# WalkerStalkerv03.net
KiCad netlist of a schematic drawn in EAGLE
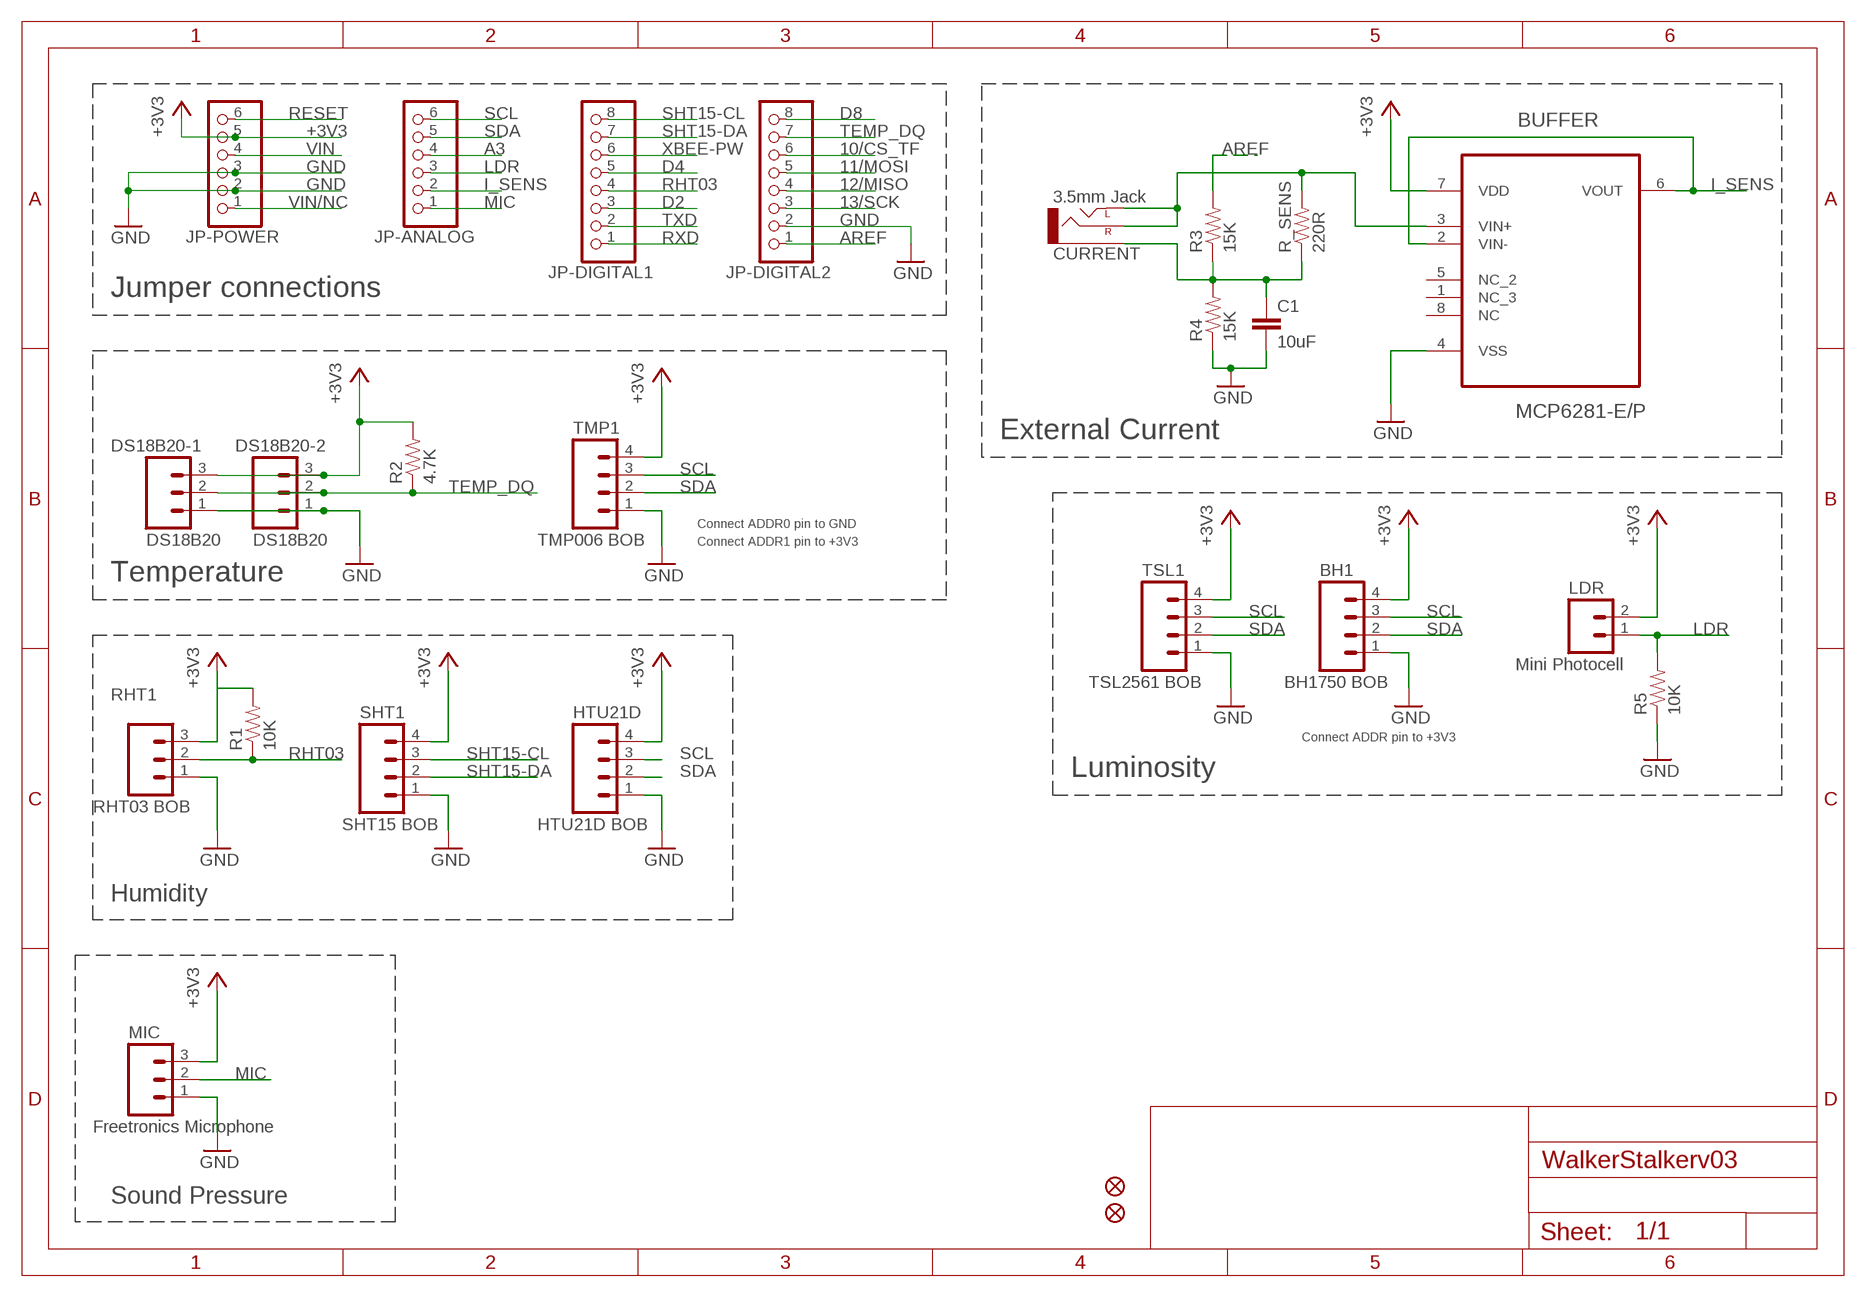
[diagram p0: schematic, sheet 1, part 1 of 2]
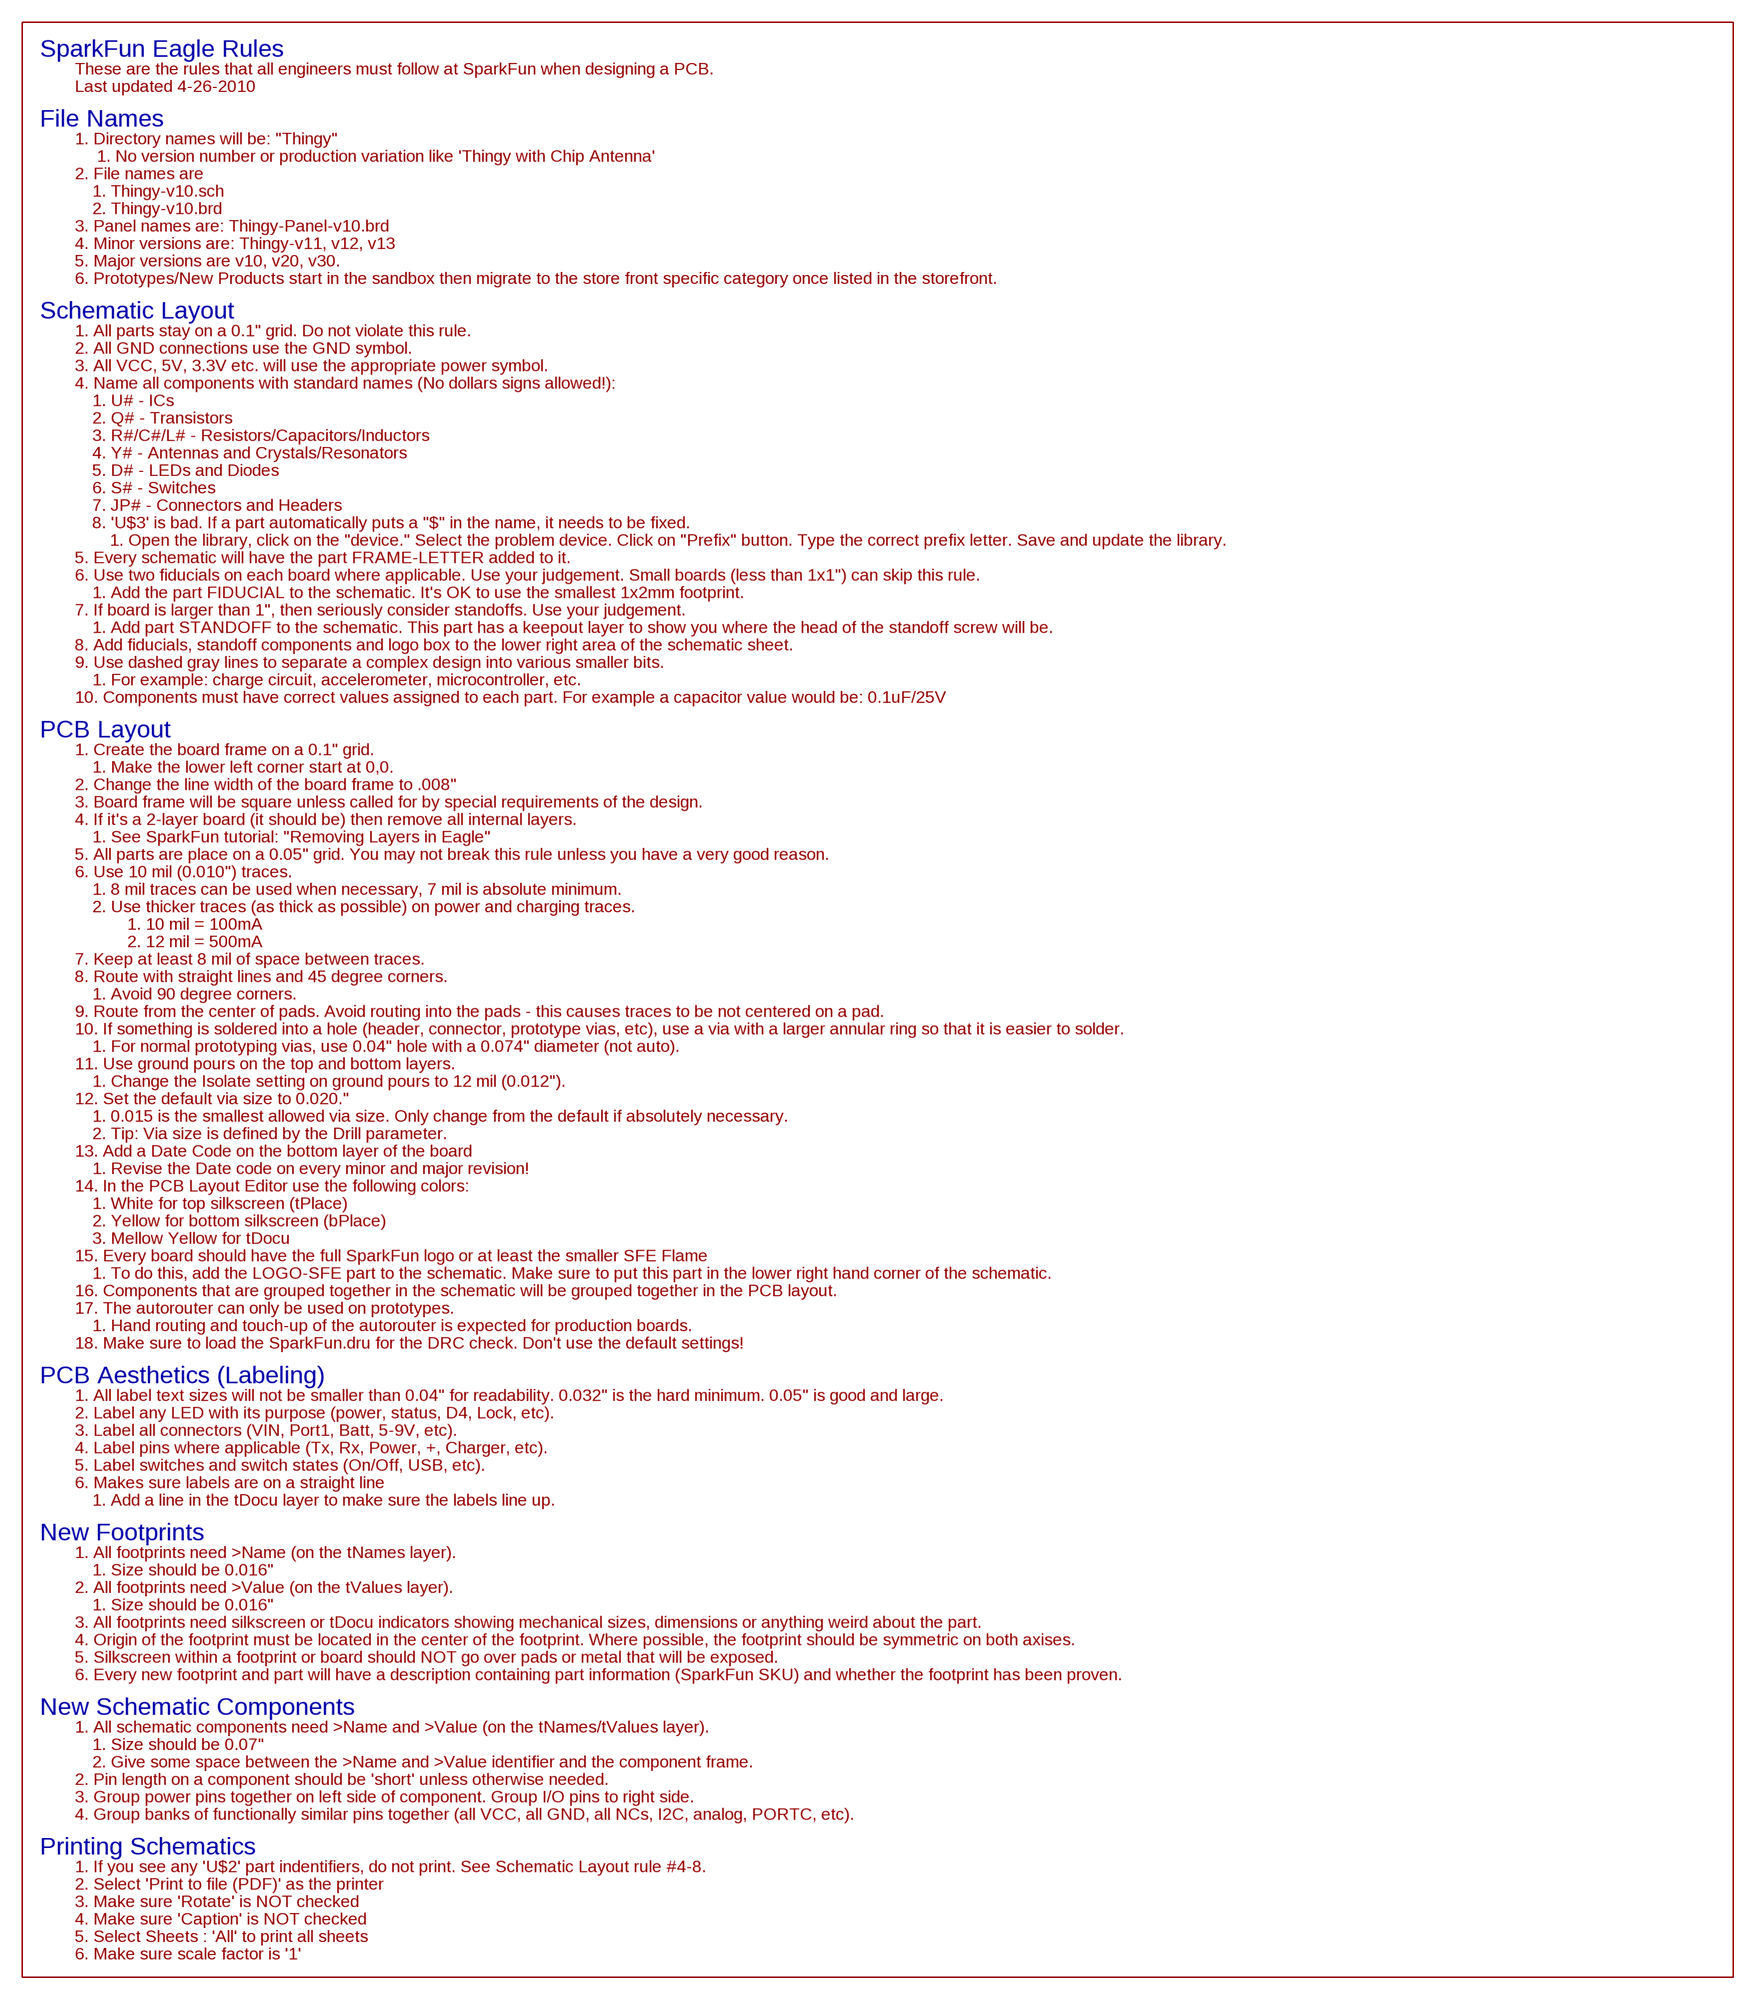
[diagram p1: schematic, sheet 1, part 2 of 2]

(export (version "E")
  (design (tool "Eeschema 10.0.6"))
  (components
    (comp (ref "BH1")
      (value "BH1750 BOB")
      (footprint "eagle-import:MOLEX-1X4")
      (libsource (lib "eagle-import") (part "M04POLAR"))
    )
    (comp (ref "BUFFER")
      (value "MCP6281-E/P")
      (footprint "eagle-import:DIP254P762X432-8")
      (libsource (lib "eagle-import") (part "MCP6281-E/P"))
    )
    (comp (ref "C1")
      (value "10uF")
      (footprint "eagle-import:1206")
      (libsource (lib "eagle-import") (part "CAP1206"))
    )
    (comp (ref "CURRENT")
      (value "3.5mm Jack")
      (footprint "eagle-import:AUDIO-JACK")
      (libsource (lib "eagle-import") (part "AUDIO-JACKPTH"))
    )
    (comp (ref "DS18B20-1")
      (value "DS18B20")
      (footprint "eagle-import:MOLEX-1X3")
      (libsource (lib "eagle-import") (part "M03POLAR"))
    )
    (comp (ref "DS18B20-2")
      (value "DS18B20")
      (footprint "eagle-import:MOLEX-1X3")
      (libsource (lib "eagle-import") (part "M03POLAR"))
    )
    (comp (ref "FID1")
      (value "FIDUCIAL1.5X3")
      (footprint "eagle-import:FIDUCIAL-1.5X3")
      (libsource (lib "eagle-import") (part "FIDUCIAL1.5X3"))
    )
    (comp (ref "FID2")
      (value "FIDUCIAL1.5X3")
      (footprint "eagle-import:FIDUCIAL-1.5X3")
      (libsource (lib "eagle-import") (part "FIDUCIAL1.5X3"))
    )
    (comp (ref "HTU21D")
      (value "HTU21D BOB")
      (footprint "eagle-import:MOLEX-1X4")
      (libsource (lib "eagle-import") (part "M04POLAR"))
    )
    (comp (ref "JP-ANALOG")
      (value "PINHD-1X6CB")
      (footprint "eagle-import:1X06-CLEANBIG")
      (libsource (lib "eagle-import") (part "PINHD-1X6CB"))
    )
    (comp (ref "JP-DIGITAL1")
      (value "PINHD-1X8CLEANBIG")
      (footprint "eagle-import:1X08-CLEANBIG")
      (libsource (lib "eagle-import") (part "PINHD-1X8CLEANBIG"))
    )
    (comp (ref "JP-DIGITAL2")
      (value "PINHD-1X8CLEANBIG")
      (footprint "eagle-import:1X08-CLEANBIG")
      (libsource (lib "eagle-import") (part "PINHD-1X8CLEANBIG"))
    )
    (comp (ref "JP-POWER")
      (value "PINHD-1X6CB")
      (footprint "eagle-import:1X06-CLEANBIG")
      (libsource (lib "eagle-import") (part "PINHD-1X6CB"))
    )
    (comp (ref "LDR")
      (value "Mini Photocell")
      (footprint "eagle-import:MOLEX-1X2")
      (libsource (lib "eagle-import") (part "M02POLAR"))
    )
    (comp (ref "MIC")
      (value "Freetronics Microphone")
      (footprint "eagle-import:MOLEX-1X3")
      (libsource (lib "eagle-import") (part "M03POLAR"))
    )
    (comp (ref "R1")
      (value "10K")
      (footprint "eagle-import:1206")
      (libsource (lib "eagle-import") (part "RESISTOR1206"))
    )
    (comp (ref "R2")
      (value "4.7K")
      (footprint "eagle-import:1206")
      (libsource (lib "eagle-import") (part "RESISTOR1206"))
    )
    (comp (ref "R3")
      (value "15K")
      (footprint "eagle-import:1206")
      (libsource (lib "eagle-import") (part "RESISTOR1206"))
    )
    (comp (ref "R4")
      (value "15K")
      (footprint "eagle-import:1206")
      (libsource (lib "eagle-import") (part "RESISTOR1206"))
    )
    (comp (ref "R5")
      (value "10K")
      (footprint "eagle-import:1206")
      (libsource (lib "eagle-import") (part "RESISTOR1206"))
    )
    (comp (ref "RHT1")
      (value "RHT03 BOB")
      (footprint "eagle-import:MOLEX-1X3")
      (libsource (lib "eagle-import") (part "M03POLAR"))
    )
    (comp (ref "R_SENS")
      (value "220R")
      (footprint "eagle-import:1206")
      (libsource (lib "eagle-import") (part "RESISTOR1206"))
    )
    (comp (ref "SHT1")
      (value "SHT15 BOB")
      (footprint "eagle-import:MOLEX-1X4")
      (libsource (lib "eagle-import") (part "M04POLAR"))
    )
    (comp (ref "TMP1")
      (value "TMP006 BOB")
      (footprint "eagle-import:MOLEX-1X4")
      (libsource (lib "eagle-import") (part "M04POLAR"))
    )
    (comp (ref "TSL1")
      (value "TSL2561 BOB")
      (footprint "eagle-import:MOLEX-1X4")
      (libsource (lib "eagle-import") (part "M04POLAR"))
    )
  )
  (nets
    (net (code "1") (name "+3V3") (class "Default")
      (node (ref "BH1") (pin "4") (pinfunction "4_4") (pintype "passive"))
      (node (ref "BUFFER") (pin "7") (pinfunction "VDD_7") (pintype "power_in"))
      (node (ref "DS18B20-1") (pin "3") (pinfunction "3_3") (pintype "passive"))
      (node (ref "DS18B20-2") (pin "3") (pinfunction "3_3") (pintype "passive"))
      (node (ref "HTU21D") (pin "4") (pinfunction "4_4") (pintype "passive"))
      (node (ref "JP-POWER") (pin "5") (pinfunction "5_5") (pintype "passive"))
      (node (ref "LDR") (pin "2") (pinfunction "2_2") (pintype "passive"))
      (node (ref "MIC") (pin "3") (pinfunction "3_3") (pintype "passive"))
      (node (ref "R1") (pin "2") (pinfunction "2_2") (pintype "passive"))
      (node (ref "R2") (pin "2") (pinfunction "2_2") (pintype "passive"))
      (node (ref "RHT1") (pin "3") (pinfunction "3_3") (pintype "passive"))
      (node (ref "SHT1") (pin "4") (pinfunction "4_4") (pintype "passive"))
      (node (ref "TMP1") (pin "4") (pinfunction "4_4") (pintype "passive"))
      (node (ref "TSL1") (pin "4") (pinfunction "4_4") (pintype "passive"))
    )
    (net (code "2") (name "/10{slash}CS_TF") (class "Default")
      (node (ref "JP-DIGITAL2") (pin "6") (pinfunction "6_6") (pintype "passive"))
    )
    (net (code "3") (name "/11{slash}MOSI") (class "Default")
      (node (ref "JP-DIGITAL2") (pin "5") (pinfunction "5_5") (pintype "passive"))
    )
    (net (code "4") (name "/12{slash}MISO") (class "Default")
      (node (ref "JP-DIGITAL2") (pin "4") (pinfunction "4_4") (pintype "passive"))
    )
    (net (code "5") (name "/13{slash}SCK") (class "Default")
      (node (ref "JP-DIGITAL2") (pin "3") (pinfunction "3_3") (pintype "passive"))
    )
    (net (code "6") (name "/A3") (class "Default")
      (node (ref "JP-ANALOG") (pin "4") (pinfunction "4_4") (pintype "passive"))
    )
    (net (code "7") (name "/AREF") (class "Default")
      (node (ref "JP-DIGITAL2") (pin "1") (pinfunction "1_1") (pintype "passive"))
      (node (ref "R3") (pin "2") (pinfunction "2_2") (pintype "passive"))
    )
    (net (code "8") (name "/D2") (class "Default")
      (node (ref "JP-DIGITAL1") (pin "3") (pinfunction "3_3") (pintype "passive"))
    )
    (net (code "9") (name "/D4") (class "Default")
      (node (ref "JP-DIGITAL1") (pin "5") (pinfunction "5_5") (pintype "passive"))
    )
    (net (code "10") (name "/D8") (class "Default")
      (node (ref "JP-DIGITAL2") (pin "8") (pinfunction "8_8") (pintype "passive"))
    )
    (net (code "11") (name "/I_SENS") (class "Default")
      (node (ref "BUFFER") (pin "2") (pinfunction "VIN-_2") (pintype "input"))
      (node (ref "BUFFER") (pin "6") (pinfunction "VOUT_6") (pintype "output"))
      (node (ref "JP-ANALOG") (pin "2") (pinfunction "2_2") (pintype "passive"))
    )
    (net (code "12") (name "/LDR") (class "Default")
      (node (ref "JP-ANALOG") (pin "3") (pinfunction "3_3") (pintype "passive"))
      (node (ref "LDR") (pin "1") (pinfunction "1_1") (pintype "passive"))
      (node (ref "R5") (pin "2") (pinfunction "2_2") (pintype "passive"))
    )
    (net (code "13") (name "/MIC") (class "Default")
      (node (ref "JP-ANALOG") (pin "1") (pinfunction "1_1") (pintype "passive"))
      (node (ref "MIC") (pin "2") (pinfunction "2_2") (pintype "passive"))
    )
    (net (code "14") (name "/RESET") (class "Default")
      (node (ref "JP-POWER") (pin "6") (pinfunction "6_6") (pintype "passive"))
    )
    (net (code "15") (name "/RHT03") (class "Default")
      (node (ref "JP-DIGITAL1") (pin "4") (pinfunction "4_4") (pintype "passive"))
      (node (ref "R1") (pin "1") (pinfunction "1_1") (pintype "passive"))
      (node (ref "RHT1") (pin "2") (pinfunction "2_2") (pintype "passive"))
    )
    (net (code "16") (name "/RXD") (class "Default")
      (node (ref "JP-DIGITAL1") (pin "1") (pinfunction "1_1") (pintype "passive"))
    )
    (net (code "17") (name "/SCL") (class "Default")
      (node (ref "BH1") (pin "3") (pinfunction "3_3") (pintype "passive"))
      (node (ref "HTU21D") (pin "3") (pinfunction "3_3") (pintype "passive"))
      (node (ref "JP-ANALOG") (pin "6") (pinfunction "6_6") (pintype "passive"))
      (node (ref "TMP1") (pin "3") (pinfunction "3_3") (pintype "passive"))
      (node (ref "TSL1") (pin "3") (pinfunction "3_3") (pintype "passive"))
    )
    (net (code "18") (name "/SDA") (class "Default")
      (node (ref "BH1") (pin "2") (pinfunction "2_2") (pintype "passive"))
      (node (ref "HTU21D") (pin "2") (pinfunction "2_2") (pintype "passive"))
      (node (ref "JP-ANALOG") (pin "5") (pinfunction "5_5") (pintype "passive"))
      (node (ref "TMP1") (pin "2") (pinfunction "2_2") (pintype "passive"))
      (node (ref "TSL1") (pin "2") (pinfunction "2_2") (pintype "passive"))
    )
    (net (code "19") (name "/SHT15-CL") (class "Default")
      (node (ref "JP-DIGITAL1") (pin "8") (pinfunction "8_8") (pintype "passive"))
      (node (ref "SHT1") (pin "3") (pinfunction "3_3") (pintype "passive"))
    )
    (net (code "20") (name "/SHT15-DA") (class "Default")
      (node (ref "JP-DIGITAL1") (pin "7") (pinfunction "7_7") (pintype "passive"))
      (node (ref "SHT1") (pin "2") (pinfunction "2_2") (pintype "passive"))
    )
    (net (code "21") (name "/TEMP_DQ") (class "Default")
      (node (ref "DS18B20-1") (pin "2") (pinfunction "2_2") (pintype "passive"))
      (node (ref "DS18B20-2") (pin "2") (pinfunction "2_2") (pintype "passive"))
      (node (ref "JP-DIGITAL2") (pin "7") (pinfunction "7_7") (pintype "passive"))
      (node (ref "R2") (pin "1") (pinfunction "1_1") (pintype "passive"))
    )
    (net (code "22") (name "/TXD") (class "Default")
      (node (ref "JP-DIGITAL1") (pin "2") (pinfunction "2_2") (pintype "passive"))
    )
    (net (code "23") (name "/VIN") (class "Default")
      (node (ref "JP-POWER") (pin "4") (pinfunction "4_4") (pintype "passive"))
    )
    (net (code "24") (name "/VIN{slash}NC") (class "Default")
      (node (ref "JP-POWER") (pin "1") (pinfunction "1_1") (pintype "passive"))
    )
    (net (code "25") (name "/XBEE-PW") (class "Default")
      (node (ref "JP-DIGITAL1") (pin "6") (pinfunction "6_6") (pintype "passive"))
    )
    (net (code "26") (name "GND") (class "Default")
      (node (ref "BH1") (pin "1") (pinfunction "1_1") (pintype "passive"))
      (node (ref "BUFFER") (pin "4") (pinfunction "VSS_4") (pintype "power_in"))
      (node (ref "C1") (pin "2") (pinfunction "2_2") (pintype "passive"))
      (node (ref "DS18B20-1") (pin "1") (pinfunction "1_1") (pintype "passive"))
      (node (ref "DS18B20-2") (pin "1") (pinfunction "1_1") (pintype "passive"))
      (node (ref "HTU21D") (pin "1") (pinfunction "1_1") (pintype "passive"))
      (node (ref "JP-DIGITAL2") (pin "2") (pinfunction "2_2") (pintype "passive"))
      (node (ref "JP-POWER") (pin "2") (pinfunction "2_2") (pintype "passive"))
      (node (ref "JP-POWER") (pin "3") (pinfunction "3_3") (pintype "passive"))
      (node (ref "MIC") (pin "1") (pinfunction "1_1") (pintype "passive"))
      (node (ref "R4") (pin "1") (pinfunction "1_1") (pintype "passive"))
      (node (ref "R5") (pin "1") (pinfunction "1_1") (pintype "passive"))
      (node (ref "RHT1") (pin "1") (pinfunction "1_1") (pintype "passive"))
      (node (ref "SHT1") (pin "1") (pinfunction "1_1") (pintype "passive"))
      (node (ref "TMP1") (pin "1") (pinfunction "1_1") (pintype "passive"))
      (node (ref "TSL1") (pin "1") (pinfunction "1_1") (pintype "passive"))
    )
    (net (code "27") (name "Net-(BUFFER-VIN+)") (class "Default")
      (node (ref "BUFFER") (pin "3") (pinfunction "VIN+_3") (pintype "input"))
      (node (ref "CURRENT") (pin "RING") (pinfunction "RIGHT_RING") (pintype "bidirectional"))
      (node (ref "CURRENT") (pin "TIP") (pinfunction "LEFT_TIP") (pintype "bidirectional"))
      (node (ref "R_SENS") (pin "2") (pinfunction "2_2") (pintype "passive"))
    )
    (net (code "28") (name "Net-(C1-Pad1)") (class "Default")
      (node (ref "C1") (pin "1") (pinfunction "1_1") (pintype "passive"))
      (node (ref "CURRENT") (pin "SLEEVE") (pinfunction "SLEEVE_SLEEVE") (pintype "bidirectional"))
      (node (ref "R3") (pin "1") (pinfunction "1_1") (pintype "passive"))
      (node (ref "R4") (pin "2") (pinfunction "2_2") (pintype "passive"))
      (node (ref "R_SENS") (pin "1") (pinfunction "1_1") (pintype "passive"))
    )
    (net (code "29") (name "unconnected-(BUFFER-NC-Pad8)") (class "Default")
      (node (ref "BUFFER") (pin "8") (pinfunction "NC_8") (pintype "no_connect"))
    )
    (net (code "30") (name "unconnected-(BUFFER-NC_2-Pad5)") (class "Default")
      (node (ref "BUFFER") (pin "5") (pinfunction "NC_2_5") (pintype "no_connect"))
    )
    (net (code "31") (name "unconnected-(BUFFER-NC_3-Pad1)") (class "Default")
      (node (ref "BUFFER") (pin "1") (pinfunction "NC_3_1") (pintype "no_connect"))
    )
  )
)
